# 1_MCU.net
KiCad netlist of a schematic drawn in Altium Designer
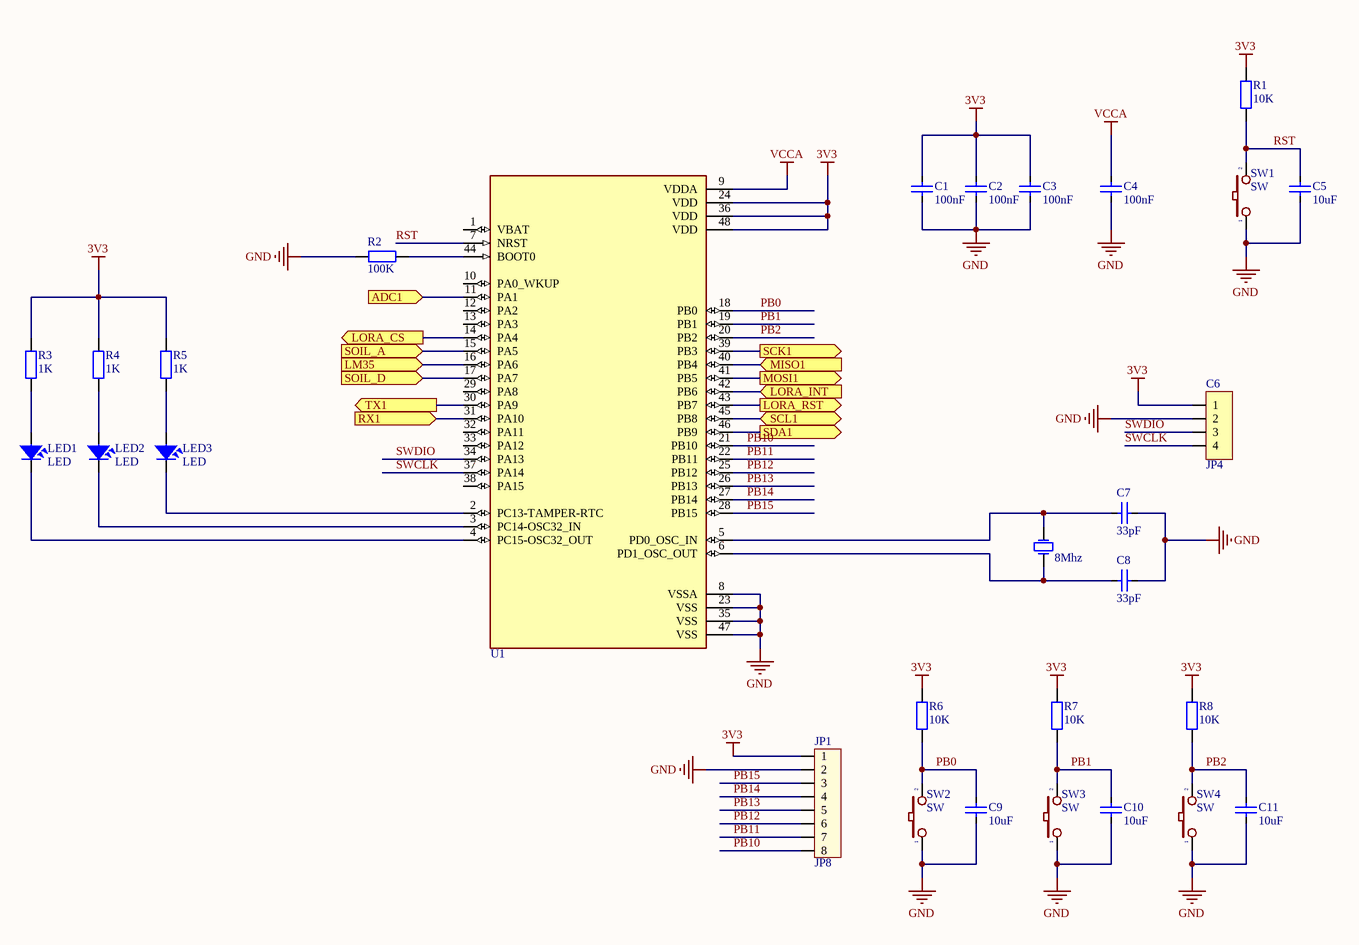
[diagram p0: [1]MCU.SchDoc]

(export (version "E")
  (design (tool "Eeschema 10.0.6"))
  (components
    (comp (ref "C1")
      (value "100nF")
      (footprint "CAP_0805")
      (description "Capacitor")
      (fields (field (name "PUBLISHER") "Altium Limited"))
      (libsource (lib "My Library") (part "CapSMD"))
    )
    (comp (ref "C2")
      (value "100nF")
      (footprint "CAP_0805")
      (description "Capacitor")
      (fields (field (name "PUBLISHER") "Altium Limited"))
      (libsource (lib "My Library") (part "CapSMD"))
    )
    (comp (ref "C3")
      (value "100nF")
      (footprint "CAP_0805")
      (description "Capacitor")
      (fields (field (name "PUBLISHER") "Altium Limited"))
      (libsource (lib "My Library") (part "CapSMD"))
    )
    (comp (ref "C4")
      (value "100nF")
      (footprint "CAP_0805")
      (description "Capacitor")
      (fields (field (name "PUBLISHER") "Altium Limited"))
      (libsource (lib "My Library") (part "CapSMD"))
    )
    (comp (ref "C5")
      (value "10uF")
      (footprint "CAP_0805")
      (description "Capacitor")
      (fields (field (name "PUBLISHER") "Altium Limited"))
      (libsource (lib "My Library") (part "CapSMD"))
    )
    (comp (ref "C6")
      (value "JP4")
      (footprint "JP4-C1T")
      (description "WR-PHD 2.54 mm Angled Socket Header")
      (fields
        (field (name "MANUFACTURER") "Würth Elektronik eiSos GmbH")
        (field (name "PARTNO") "613004143121")
        (field (name "CREATED BY") "Karrer Zheng")
      )
      (libsource (lib "My Library") (part "JP4"))
    )
    (comp (ref "C7")
      (value "33pF")
      (footprint "CAP_0805")
      (description "Capacitor")
      (fields (field (name "PUBLISHER") "Altium Limited"))
      (libsource (lib "My Library") (part "CapSMD"))
    )
    (comp (ref "C8")
      (value "33pF")
      (footprint "CAP_0805")
      (description "Capacitor")
      (fields (field (name "PUBLISHER") "Altium Limited"))
      (libsource (lib "My Library") (part "CapSMD"))
    )
    (comp (ref "C9")
      (value "10uF")
      (footprint "CAP_0805")
      (description "Capacitor")
      (fields (field (name "PUBLISHER") "Altium Limited"))
      (libsource (lib "My Library") (part "CapSMD"))
    )
    (comp (ref "C10")
      (value "10uF")
      (footprint "CAP_0805")
      (description "Capacitor")
      (fields (field (name "PUBLISHER") "Altium Limited"))
      (libsource (lib "My Library") (part "CapSMD"))
    )
    (comp (ref "C11")
      (value "10uF")
      (footprint "CAP_0805")
      (description "Capacitor")
      (fields (field (name "PUBLISHER") "Altium Limited"))
      (libsource (lib "My Library") (part "CapSMD"))
    )
    (comp (ref "JP1")
      (value "JP8")
      (footprint "CON8")
      (description "Connector 8")
      (libsource (lib "My Library") (part "Con8"))
    )
    (comp (ref "LED1")
      (value "LED")
      (footprint "LED-0805-Blue")
      (description "LED Single colour Green and Red")
      (libsource (lib "My Library") (part "LED"))
    )
    (comp (ref "LED2")
      (value "LED")
      (footprint "LED-0805-Blue")
      (description "LED Single colour Green and Red")
      (libsource (lib "My Library") (part "LED"))
    )
    (comp (ref "LED3")
      (value "LED")
      (footprint "LED-0805-Blue")
      (description "LED Single colour Green and Red")
      (libsource (lib "My Library") (part "LED"))
    )
    (comp (ref "R1")
      (value "10K")
      (footprint "RES-SMD-0805")
      (description "Resistor SMD")
      (fields
        (field (name "MANUFACTURER") "Generic Components")
        (field (name "PUBLISHER") "Altium Hobart Technology Centre")
      )
      (libsource (lib "My Library") (part "Resistor - SMD"))
    )
    (comp (ref "R2")
      (value "100K")
      (footprint "RES_SMD_0805")
      (description "Resistor SMD")
      (fields
        (field (name "MANUFACTURER") "Generic Components")
        (field (name "PUBLISHER") "Altium Hobart Technology Centre")
      )
      (libsource (lib "My Library") (part "Resistor - SMD"))
    )
    (comp (ref "R3")
      (value "1K")
      (footprint "RES_SMD_0805")
      (description "Resistor SMD")
      (fields
        (field (name "MANUFACTURER") "Generic Components")
        (field (name "PUBLISHER") "Altium Hobart Technology Centre")
      )
      (libsource (lib "My Library") (part "Resistor - SMD"))
    )
    (comp (ref "R4")
      (value "1K")
      (footprint "RES_SMD_0805")
      (description "Resistor SMD")
      (fields
        (field (name "MANUFACTURER") "Generic Components")
        (field (name "PUBLISHER") "Altium Hobart Technology Centre")
      )
      (libsource (lib "My Library") (part "Resistor - SMD"))
    )
    (comp (ref "R5")
      (value "1K")
      (footprint "RES_SMD_0805")
      (description "Resistor SMD")
      (fields
        (field (name "MANUFACTURER") "Generic Components")
        (field (name "PUBLISHER") "Altium Hobart Technology Centre")
      )
      (libsource (lib "My Library") (part "Resistor - SMD"))
    )
    (comp (ref "R6")
      (value "10K")
      (footprint "RES-SMD-0805")
      (description "Resistor SMD")
      (fields
        (field (name "MANUFACTURER") "Generic Components")
        (field (name "PUBLISHER") "Altium Hobart Technology Centre")
      )
      (libsource (lib "My Library") (part "Resistor - SMD"))
    )
    (comp (ref "R7")
      (value "10K")
      (footprint "RES-SMD-0805")
      (description "Resistor SMD")
      (fields
        (field (name "MANUFACTURER") "Generic Components")
        (field (name "PUBLISHER") "Altium Hobart Technology Centre")
      )
      (libsource (lib "My Library") (part "Resistor - SMD"))
    )
    (comp (ref "R8")
      (value "10K")
      (footprint "RES-SMD-0805")
      (description "Resistor SMD")
      (fields
        (field (name "MANUFACTURER") "Generic Components")
        (field (name "PUBLISHER") "Altium Hobart Technology Centre")
      )
      (libsource (lib "My Library") (part "Resistor - SMD"))
    )
    (comp (ref "SW1")
      (value "SW")
      (footprint "SW2")
      (description "Switch button 2 pin")
      (libsource (lib "My Library") (part "SW2"))
    )
    (comp (ref "SW2")
      (value "SW")
      (footprint "SW2")
      (description "Switch button 2 pin")
      (libsource (lib "My Library") (part "SW2"))
    )
    (comp (ref "SW3")
      (value "SW")
      (footprint "SW2")
      (description "Switch button 2 pin")
      (libsource (lib "My Library") (part "SW2"))
    )
    (comp (ref "SW4")
      (value "SW")
      (footprint "SW2")
      (description "Switch button 2 pin")
      (libsource (lib "My Library") (part "SW2"))
    )
    (comp (ref "U1")
      (value "STM32")
      (footprint "LQFP 48")
      (description "STM32 ARM-based 32-bit MCU with 64 Kbytes Flash, 64-pin LQFP, Industrial Temperature")
      (libsource (lib "My Library") (part "STM32F103C8T6"))
    )
    (comp (ref "Y1")
      (value "8Mhz")
      (footprint "XTAL")
      (description "Crystal Oscillator")
      (fields (field (name "PUBLISHER") "Altium Limited"))
      (libsource (lib "My Library") (part "XTAL"))
    )
  )
  (nets
    (net (code "1") (name "/ADC1") (class "Default")
      (node (ref "U1") (pin "11") (pinfunction "PA1_11") (pintype "bidirectional"))
    )
    (net (code "2") (name "/LM35") (class "Default")
      (node (ref "U1") (pin "16") (pinfunction "PA6_16") (pintype "bidirectional"))
    )
    (net (code "3") (name "/LORA_CS") (class "Default")
      (node (ref "U1") (pin "14") (pinfunction "PA4_14") (pintype "bidirectional"))
    )
    (net (code "4") (name "/LORA_INT") (class "Default")
      (node (ref "U1") (pin "42") (pinfunction "PB6_42") (pintype "bidirectional"))
    )
    (net (code "5") (name "/LORA_RST") (class "Default")
      (node (ref "U1") (pin "43") (pinfunction "PB7_43") (pintype "bidirectional"))
    )
    (net (code "6") (name "/MISO1") (class "Default")
      (node (ref "U1") (pin "40") (pinfunction "PB4_40") (pintype "bidirectional"))
    )
    (net (code "7") (name "/MOSI1") (class "Default")
      (node (ref "U1") (pin "41") (pinfunction "PB5_41") (pintype "bidirectional"))
    )
    (net (code "8") (name "/PB0") (class "Default")
      (node (ref "C9") (pin "2") (pinfunction "2_2") (pintype "passive"))
      (node (ref "R6") (pin "2") (pinfunction "2_2") (pintype "passive"))
      (node (ref "SW2") (pin "2") (pinfunction "2_2") (pintype "passive"))
      (node (ref "U1") (pin "18") (pinfunction "PB0_18") (pintype "bidirectional"))
    )
    (net (code "9") (name "/PB1") (class "Default")
      (node (ref "C10") (pin "2") (pinfunction "2_2") (pintype "passive"))
      (node (ref "R7") (pin "2") (pinfunction "2_2") (pintype "passive"))
      (node (ref "SW3") (pin "2") (pinfunction "2_2") (pintype "passive"))
      (node (ref "U1") (pin "19") (pinfunction "PB1_19") (pintype "bidirectional"))
    )
    (net (code "10") (name "/PB2") (class "Default")
      (node (ref "C11") (pin "2") (pinfunction "2_2") (pintype "passive"))
      (node (ref "R8") (pin "2") (pinfunction "2_2") (pintype "passive"))
      (node (ref "SW4") (pin "2") (pinfunction "2_2") (pintype "passive"))
      (node (ref "U1") (pin "20") (pinfunction "PB2_20") (pintype "bidirectional"))
    )
    (net (code "11") (name "/PB10") (class "Default")
      (node (ref "JP1") (pin "8") (pinfunction "8_8") (pintype "passive"))
      (node (ref "U1") (pin "21") (pinfunction "PB10_21") (pintype "bidirectional"))
    )
    (net (code "12") (name "/PB11") (class "Default")
      (node (ref "JP1") (pin "7") (pinfunction "7_7") (pintype "passive"))
      (node (ref "U1") (pin "22") (pinfunction "PB11_22") (pintype "bidirectional"))
    )
    (net (code "13") (name "/PB12") (class "Default")
      (node (ref "JP1") (pin "6") (pinfunction "6_6") (pintype "passive"))
      (node (ref "U1") (pin "25") (pinfunction "PB12_25") (pintype "bidirectional"))
    )
    (net (code "14") (name "/PB13") (class "Default")
      (node (ref "JP1") (pin "5") (pinfunction "5_5") (pintype "passive"))
      (node (ref "U1") (pin "26") (pinfunction "PB13_26") (pintype "bidirectional"))
    )
    (net (code "15") (name "/PB14") (class "Default")
      (node (ref "JP1") (pin "4") (pinfunction "4_4") (pintype "passive"))
      (node (ref "U1") (pin "27") (pinfunction "PB14_27") (pintype "bidirectional"))
    )
    (net (code "16") (name "/PB15") (class "Default")
      (node (ref "JP1") (pin "3") (pinfunction "3_3") (pintype "passive"))
      (node (ref "U1") (pin "28") (pinfunction "PB15_28") (pintype "bidirectional"))
    )
    (net (code "17") (name "/RST") (class "Default")
      (node (ref "C5") (pin "2") (pinfunction "2_2") (pintype "passive"))
      (node (ref "R1") (pin "2") (pinfunction "2_2") (pintype "passive"))
      (node (ref "SW1") (pin "2") (pinfunction "2_2") (pintype "passive"))
      (node (ref "U1") (pin "7") (pinfunction "NRST_7") (pintype "input"))
    )
    (net (code "18") (name "/RX1") (class "Default")
      (node (ref "U1") (pin "31") (pinfunction "PA10_31") (pintype "bidirectional"))
    )
    (net (code "19") (name "/SCK1") (class "Default")
      (node (ref "U1") (pin "39") (pinfunction "PB3_39") (pintype "bidirectional"))
    )
    (net (code "20") (name "/SCL1") (class "Default")
      (node (ref "U1") (pin "45") (pinfunction "PB8_45") (pintype "bidirectional"))
    )
    (net (code "21") (name "/SDA1") (class "Default")
      (node (ref "U1") (pin "46") (pinfunction "PB9_46") (pintype "bidirectional"))
    )
    (net (code "22") (name "/SOIL_A") (class "Default")
      (node (ref "U1") (pin "15") (pinfunction "PA5_15") (pintype "bidirectional"))
    )
    (net (code "23") (name "/SOIL_D") (class "Default")
      (node (ref "U1") (pin "17") (pinfunction "PA7_17") (pintype "bidirectional"))
    )
    (net (code "24") (name "/SWCLK") (class "Default")
      (node (ref "C6") (pin "4") (pinfunction "4_4") (pintype "passive"))
      (node (ref "U1") (pin "37") (pinfunction "PA14_37") (pintype "bidirectional"))
    )
    (net (code "25") (name "/SWDIO") (class "Default")
      (node (ref "C6") (pin "3") (pinfunction "3_3") (pintype "passive"))
      (node (ref "U1") (pin "34") (pinfunction "PA13_34") (pintype "bidirectional"))
    )
    (net (code "26") (name "/TX1") (class "Default")
      (node (ref "U1") (pin "30") (pinfunction "PA9_30") (pintype "bidirectional"))
    )
    (net (code "27") (name "3V3") (class "Default")
      (node (ref "C1") (pin "2") (pinfunction "2_2") (pintype "passive"))
      (node (ref "C2") (pin "2") (pinfunction "2_2") (pintype "passive"))
      (node (ref "C3") (pin "2") (pinfunction "2_2") (pintype "passive"))
      (node (ref "C6") (pin "1") (pinfunction "1_1") (pintype "passive"))
      (node (ref "JP1") (pin "1") (pinfunction "1_1") (pintype "passive"))
      (node (ref "R1") (pin "1") (pinfunction "1_1") (pintype "passive"))
      (node (ref "R3") (pin "1") (pinfunction "1_1") (pintype "passive"))
      (node (ref "R4") (pin "1") (pinfunction "1_1") (pintype "passive"))
      (node (ref "R5") (pin "1") (pinfunction "1_1") (pintype "passive"))
      (node (ref "R6") (pin "1") (pinfunction "1_1") (pintype "passive"))
      (node (ref "R7") (pin "1") (pinfunction "1_1") (pintype "passive"))
      (node (ref "R8") (pin "1") (pinfunction "1_1") (pintype "passive"))
      (node (ref "U1") (pin "24") (pinfunction "VDD_24") (pintype "power_in"))
      (node (ref "U1") (pin "36") (pinfunction "VDD_36") (pintype "power_in"))
      (node (ref "U1") (pin "48") (pinfunction "VDD_48") (pintype "power_in"))
    )
    (net (code "28") (name "GND") (class "Default")
      (node (ref "C1") (pin "1") (pinfunction "1_1") (pintype "passive"))
      (node (ref "C10") (pin "1") (pinfunction "1_1") (pintype "passive"))
      (node (ref "C11") (pin "1") (pinfunction "1_1") (pintype "passive"))
      (node (ref "C2") (pin "1") (pinfunction "1_1") (pintype "passive"))
      (node (ref "C3") (pin "1") (pinfunction "1_1") (pintype "passive"))
      (node (ref "C4") (pin "1") (pinfunction "1_1") (pintype "passive"))
      (node (ref "C5") (pin "1") (pinfunction "1_1") (pintype "passive"))
      (node (ref "C6") (pin "2") (pinfunction "2_2") (pintype "passive"))
      (node (ref "C7") (pin "2") (pinfunction "2_2") (pintype "passive"))
      (node (ref "C8") (pin "2") (pinfunction "2_2") (pintype "passive"))
      (node (ref "C9") (pin "1") (pinfunction "1_1") (pintype "passive"))
      (node (ref "JP1") (pin "2") (pinfunction "2_2") (pintype "passive"))
      (node (ref "R2") (pin "2") (pinfunction "2_2") (pintype "passive"))
      (node (ref "SW1") (pin "1") (pinfunction "1_1") (pintype "passive"))
      (node (ref "SW2") (pin "1") (pinfunction "1_1") (pintype "passive"))
      (node (ref "SW3") (pin "1") (pinfunction "1_1") (pintype "passive"))
      (node (ref "SW4") (pin "1") (pinfunction "1_1") (pintype "passive"))
      (node (ref "U1") (pin "23") (pinfunction "VSS_23") (pintype "power_in"))
      (node (ref "U1") (pin "35") (pinfunction "VSS_35") (pintype "power_in"))
      (node (ref "U1") (pin "47") (pinfunction "VSS_47") (pintype "power_in"))
      (node (ref "U1") (pin "8") (pinfunction "VSSA_8") (pintype "power_in"))
    )
    (net (code "29") (name "Net-(LED1-Pad1)") (class "Default")
      (node (ref "LED1") (pin "1") (pinfunction "1_1") (pintype "passive"))
      (node (ref "R3") (pin "2") (pinfunction "2_2") (pintype "passive"))
    )
    (net (code "30") (name "Net-(LED2-Pad1)") (class "Default")
      (node (ref "LED2") (pin "1") (pinfunction "1_1") (pintype "passive"))
      (node (ref "R4") (pin "2") (pinfunction "2_2") (pintype "passive"))
    )
    (net (code "31") (name "Net-(LED3-Pad1)") (class "Default")
      (node (ref "LED3") (pin "1") (pinfunction "1_1") (pintype "passive"))
      (node (ref "R5") (pin "2") (pinfunction "2_2") (pintype "passive"))
    )
    (net (code "32") (name "Net-(U1-BOOT0)") (class "Default")
      (node (ref "R2") (pin "1") (pinfunction "1_1") (pintype "passive"))
      (node (ref "U1") (pin "44") (pinfunction "BOOT0_44") (pintype "input"))
    )
    (net (code "33") (name "Net-(U1-PC13-TAMPER-RTC)") (class "Default")
      (node (ref "LED3") (pin "2") (pinfunction "2_2") (pintype "passive"))
      (node (ref "U1") (pin "2") (pinfunction "PC13-TAMPER-RTC_2") (pintype "bidirectional"))
    )
    (net (code "34") (name "Net-(U1-PC14-OSC32_IN)") (class "Default")
      (node (ref "LED2") (pin "2") (pinfunction "2_2") (pintype "passive"))
      (node (ref "U1") (pin "3") (pinfunction "PC14-OSC32_IN_3") (pintype "bidirectional"))
    )
    (net (code "35") (name "Net-(U1-PC15-OSC32_OUT)") (class "Default")
      (node (ref "LED1") (pin "2") (pinfunction "2_2") (pintype "passive"))
      (node (ref "U1") (pin "4") (pinfunction "PC15-OSC32_OUT_4") (pintype "bidirectional"))
    )
    (net (code "36") (name "Net-(U1-PD0_OSC_IN)") (class "Default")
      (node (ref "C7") (pin "1") (pinfunction "1_1") (pintype "passive"))
      (node (ref "U1") (pin "5") (pinfunction "PD0_OSC_IN_5") (pintype "bidirectional"))
      (node (ref "Y1") (pin "2") (pinfunction "OSC2_2") (pintype "passive"))
    )
    (net (code "37") (name "Net-(U1-PD1_OSC_OUT)") (class "Default")
      (node (ref "C8") (pin "1") (pinfunction "1_1") (pintype "passive"))
      (node (ref "U1") (pin "6") (pinfunction "PD1_OSC_OUT_6") (pintype "bidirectional"))
      (node (ref "Y1") (pin "1") (pinfunction "OSC1_1") (pintype "passive"))
    )
    (net (code "38") (name "VCCA") (class "Default")
      (node (ref "C4") (pin "2") (pinfunction "2_2") (pintype "passive"))
      (node (ref "U1") (pin "9") (pinfunction "VDDA_9") (pintype "power_in"))
    )
    (net (code "39") (name "unconnected-(U1-PA0_WKUP-Pad10)") (class "Default")
      (node (ref "U1") (pin "10") (pinfunction "PA0_WKUP_10") (pintype "bidirectional"))
    )
    (net (code "40") (name "unconnected-(U1-PA2-Pad12)") (class "Default")
      (node (ref "U1") (pin "12") (pinfunction "PA2_12") (pintype "bidirectional"))
    )
    (net (code "41") (name "unconnected-(U1-PA3-Pad13)") (class "Default")
      (node (ref "U1") (pin "13") (pinfunction "PA3_13") (pintype "bidirectional"))
    )
    (net (code "42") (name "unconnected-(U1-PA8-Pad29)") (class "Default")
      (node (ref "U1") (pin "29") (pinfunction "PA8_29") (pintype "bidirectional"))
    )
    (net (code "43") (name "unconnected-(U1-PA11-Pad32)") (class "Default")
      (node (ref "U1") (pin "32") (pinfunction "PA11_32") (pintype "bidirectional"))
    )
    (net (code "44") (name "unconnected-(U1-PA12-Pad33)") (class "Default")
      (node (ref "U1") (pin "33") (pinfunction "PA12_33") (pintype "bidirectional"))
    )
    (net (code "45") (name "unconnected-(U1-PA15-Pad38)") (class "Default")
      (node (ref "U1") (pin "38") (pinfunction "PA15_38") (pintype "bidirectional"))
    )
    (net (code "46") (name "unconnected-(U1-VBAT-Pad1)") (class "Default")
      (node (ref "U1") (pin "1") (pinfunction "VBAT_1") (pintype "bidirectional"))
    )
  )
)
